# CAN.net
KiCad netlist of a schematic drawn in Altium Designer
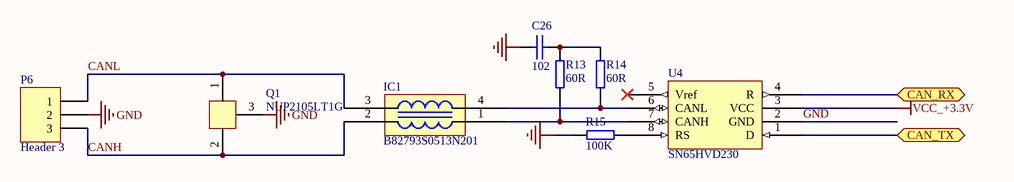
[diagram p0: CAN.SchDoc]

(export (version "E")
  (design (tool "Eeschema 10.0.6"))
  (components
    (comp (ref "C26")
      (value "102")
      (footprint "0603C")
      (description "Capacitor")
      (libsource (lib "*") (part "CAP"))
    )
    (comp (ref "IC1")
      (value "B82793S0513N201")
      (footprint "EPCOS_Chokes")
      (description "Common-mode chokes, ring core")
      (libsource (lib "*") (part "EPCOS Chokes"))
    )
    (comp (ref "P6")
      (value "Header 3")
      (footprint "XH254-3P")
      (description "Header, 3-Pin")
      (fields (field (name "PUBLISHER") "Altium Limited"))
      (libsource (lib "Miscellaneous Connectors") (part "Header 3"))
    )
    (comp (ref "Q1") (value "NUP2105LT1G") (footprint "SOT23") (libsource (lib "*") (part "SOT23")))
    (comp (ref "R13") (value "60R") (footprint "0603R") (libsource (lib "*") (part "RES2A")))
    (comp (ref "R14") (value "60R") (footprint "0603R") (libsource (lib "*") (part "RES2A")))
    (comp (ref "R15") (value "100K") (footprint "0603R") (libsource (lib "*") (part "RES2A")))
    (comp (ref "U4")
      (value "SN65HVD230")
      (footprint "SOP8")
      (libsource (lib "STR910_SCHLIB") (part "SN65HVD230D"))
    )
  )
  (nets
    (net (code "1") (name "/CANH") (class "Default")
      (node (ref "IC1") (pin "2") (pintype "passive"))
      (node (ref "P6") (pin "3") (pinfunction "3_3") (pintype "passive"))
      (node (ref "Q1") (pin "2") (pintype "passive"))
    )
    (net (code "2") (name "/CANL") (class "Default")
      (node (ref "IC1") (pin "3") (pintype "passive"))
      (node (ref "P6") (pin "1") (pinfunction "1_1") (pintype "passive"))
      (node (ref "Q1") (pin "1") (pintype "passive"))
    )
    (net (code "3") (name "/CAN_RX") (class "Default")
      (node (ref "U4") (pin "4") (pinfunction "R_4") (pintype "output"))
    )
    (net (code "4") (name "/CAN_TX") (class "Default")
      (node (ref "U4") (pin "1") (pinfunction "D_1") (pintype "input"))
    )
    (net (code "5") (name "GND") (class "Default")
      (node (ref "C26") (pin "1") (pinfunction "1_1") (pintype "passive"))
      (node (ref "P6") (pin "2") (pinfunction "2_2") (pintype "passive"))
      (node (ref "Q1") (pin "3") (pintype "passive"))
      (node (ref "R15") (pin "2") (pintype "passive"))
      (node (ref "U4") (pin "2") (pinfunction "GND_2") (pintype "power_in"))
    )
    (net (code "6") (name "Net-(C26-Pad2)") (class "Default")
      (node (ref "C26") (pin "2") (pinfunction "2_2") (pintype "passive"))
      (node (ref "R13") (pin "2") (pintype "passive"))
      (node (ref "R14") (pin "2") (pintype "passive"))
    )
    (net (code "7") (name "Net-(U4-CANH)") (class "Default")
      (node (ref "IC1") (pin "1") (pintype "passive"))
      (node (ref "R13") (pin "1") (pintype "passive"))
      (node (ref "U4") (pin "7") (pinfunction "CANH_7") (pintype "bidirectional"))
    )
    (net (code "8") (name "Net-(U4-CANL)") (class "Default")
      (node (ref "IC1") (pin "4") (pintype "passive"))
      (node (ref "R14") (pin "1") (pintype "passive"))
      (node (ref "U4") (pin "6") (pinfunction "CANL_6") (pintype "bidirectional"))
    )
    (net (code "9") (name "Net-(U4-RS)") (class "Default")
      (node (ref "R15") (pin "1") (pintype "passive"))
      (node (ref "U4") (pin "8") (pinfunction "RS_8") (pintype "input"))
    )
    (net (code "10") (name "VCC_+3.3V") (class "Default")
      (node (ref "U4") (pin "3") (pinfunction "VCC_3") (pintype "power_in"))
    )
    (net (code "11") (name "unconnected-(U4-Vref-Pad5)") (class "Default")
      (node (ref "U4") (pin "5") (pinfunction "Vref_5") (pintype "output+no_connect"))
    )
  )
)
